# HIVE_BOARD_TOP.net
KiCad netlist of a schematic drawn in Altium Designer
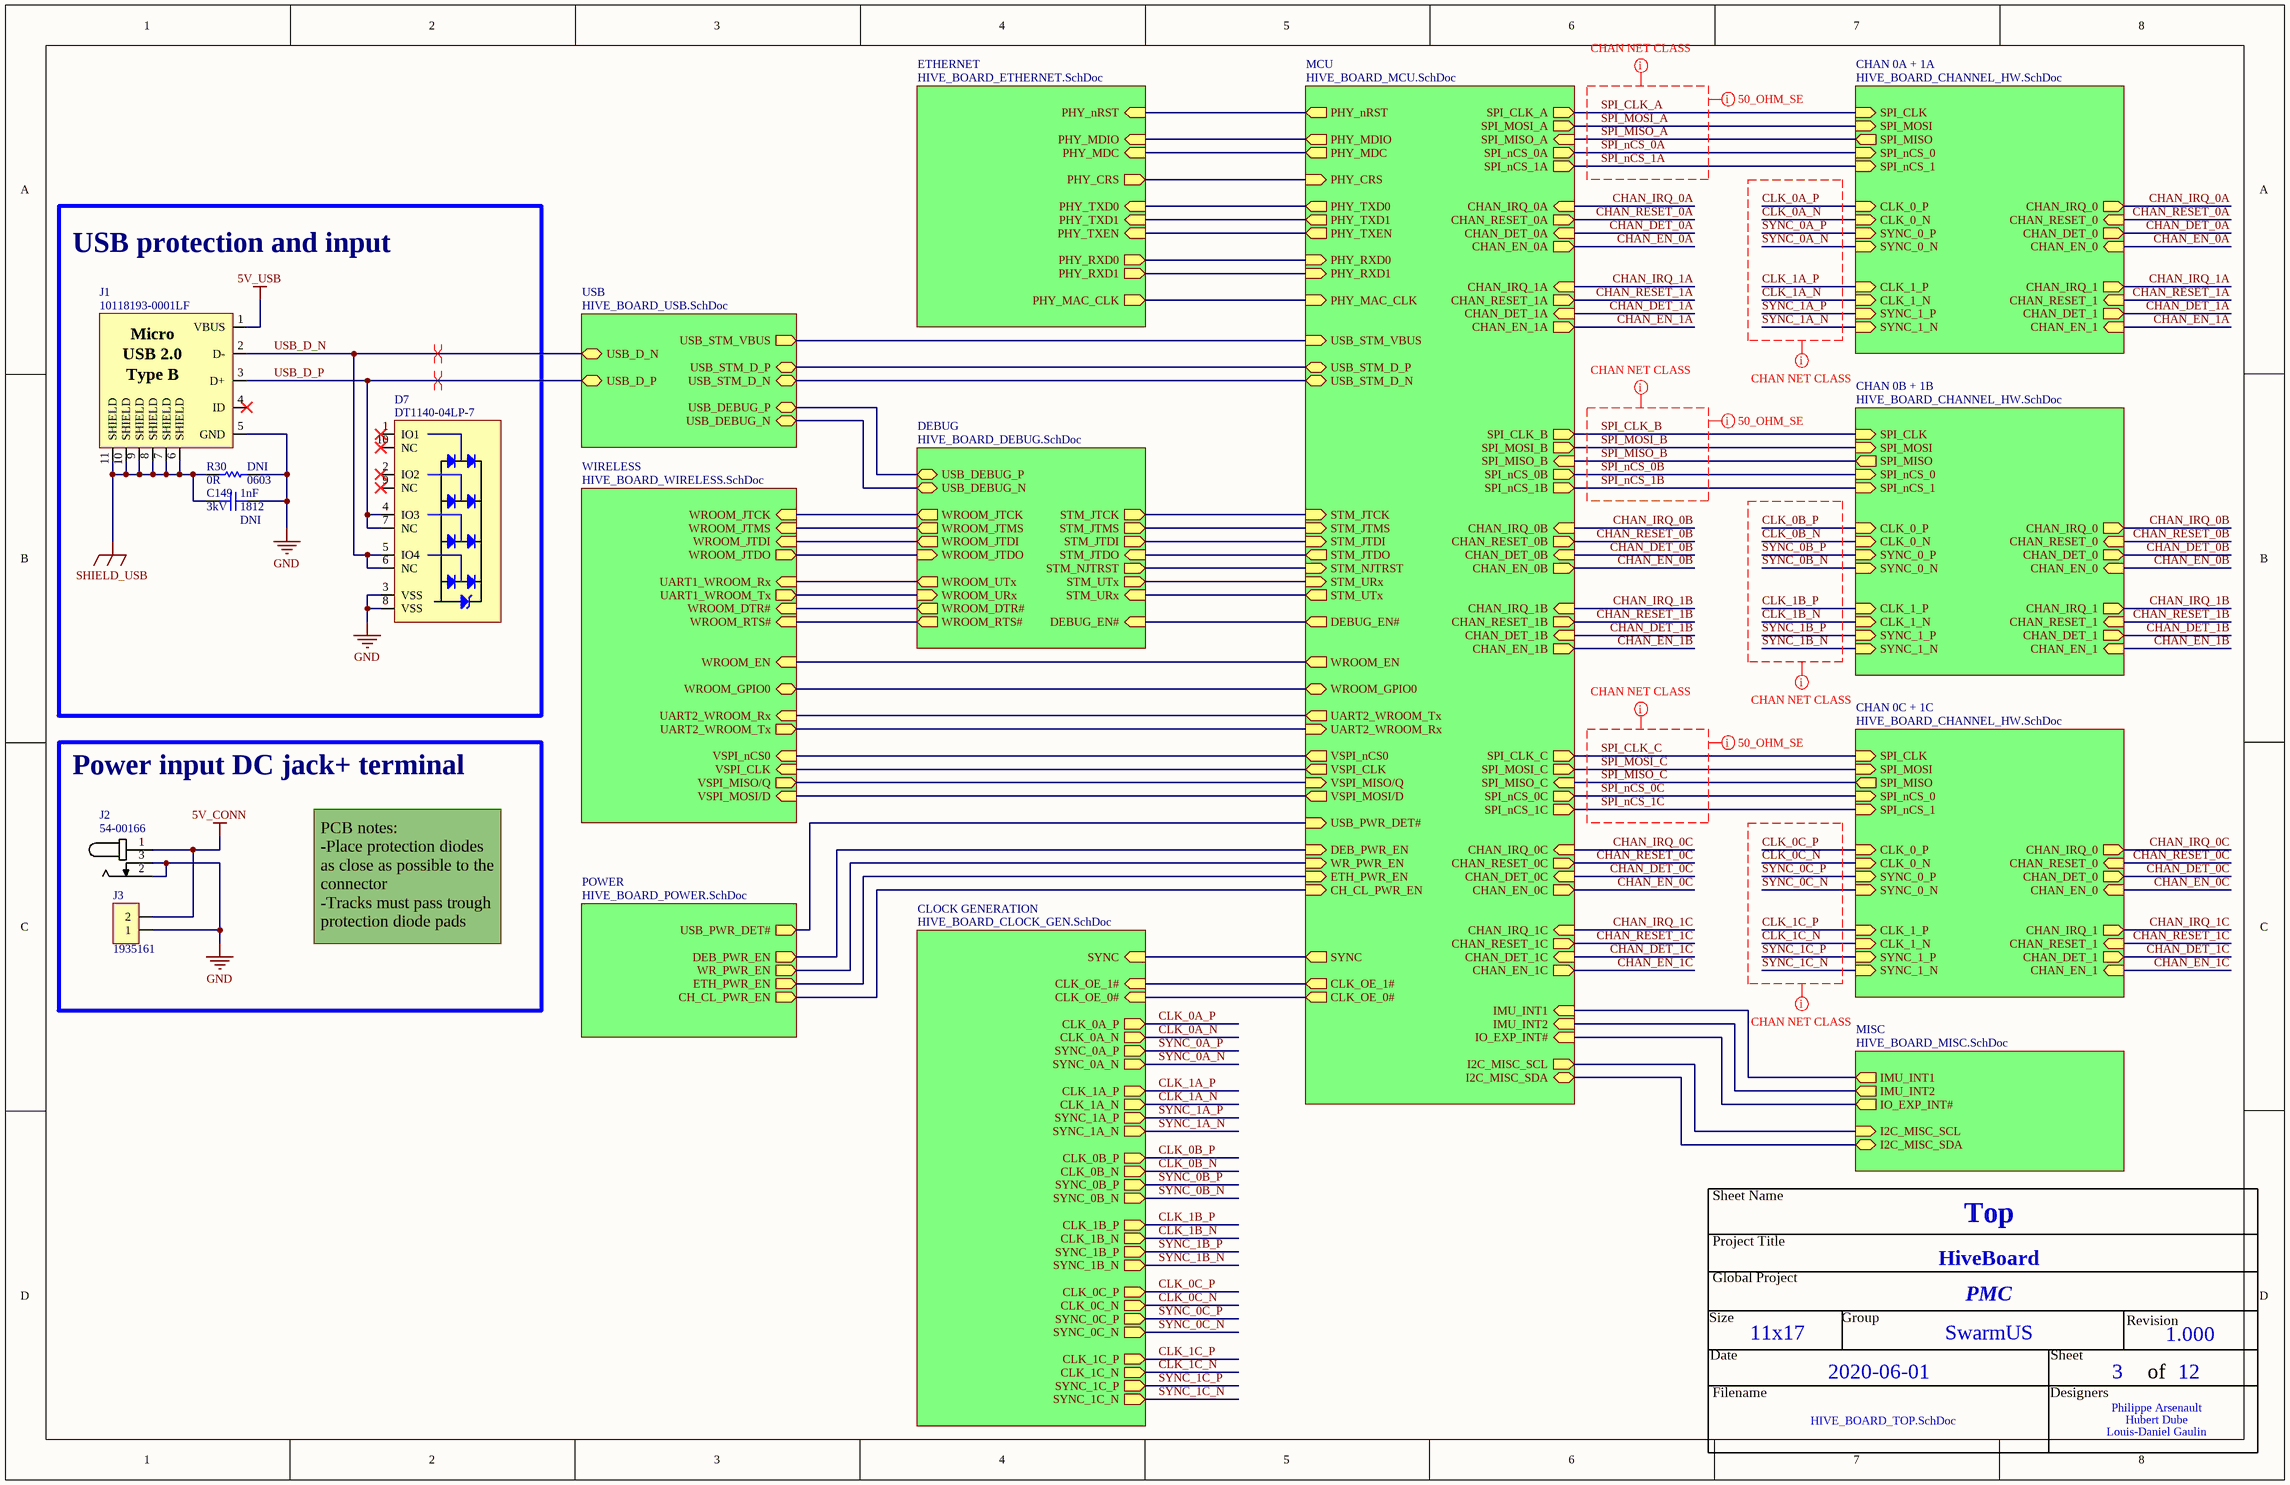
[diagram p0: HIVE_BOARD_TOP.SchDoc]

(export (version "E")
  (design (tool "Eeschema 10.0.6"))
  (components
    (comp (ref "C149")
      (value "1nF")
      (footprint "CAP_CER_1812")
      (description "CAP - CER 1000pF ±10% 3000V X7R")
      (fields
        (field (name "TOLERANCE") "10%")
        (field (name "PACKAGE") "1812")
        (field (name "VOLTAGE RATING") "3kV")
        (field (name "ASSEMBLY NOTE") "DNI")
        (field (name "Comment") "885342211009")
        (field (name "CREATEDBY/DATE") "Hubert Dube - 03/02/2021")
        (field (name "VERIFIEDBY") "Philippe Asenault - 08-02-2021")
      )
      (libsource (lib "SWARMUS_LIB") (part "CAP_CER_885342211009"))
    )
    (comp (ref "D7")
      (value "DT1140-04LP-7")
      (footprint "TVS_DATA_DT1140-04LP-7")
      (description "TVS - DIODE 5.5V 10V - 10-UFDFN")
      (fields
        (field (name "CREATEDBY/DATE") "Joël Lemay 2019-11-20")
        (field (name "VERIFIEDBY") "C.Paulin - 21/11/2019")
      )
      (libsource (lib "GRAMS_MASTER_LIB") (part "TVS_DATA_DT1140-04LP-7"))
    )
    (comp (ref "J1")
      (value "10118193-0001LF")
      (footprint "CON_USB_10118194-0001LF")
      (description "CON - USB MICRO B RECPT SMT R/A - 4PIN")
      (fields
        (field (name "CREATEDBY/DATE") "Louis-Daniel Gaulin / 31-05-2021")
        (field (name "VERIFIEDBY") "Philippe Arsenault/2021-06-07")
      )
      (libsource (lib "SWARMUS_LIB") (part "CON_USB_2.0_MicroB_10118193-0001LF"))
    )
    (comp (ref "J2")
      (value "54-00166")
      (footprint "CON_PWR_PJ-002A")
      (description "CON -  PWR JACK 231X5.5MM SOLDER RIGHT ANGLE - TH")
      (fields
        (field (name "CREATEDBY/DATE") "L-D Gaulin / 23-05-2021")
        (field (name "VERIFIEDBY") "Philippe Arsenault/24-05-2021")
      )
      (libsource (lib "SWARMUS_LIB") (part "CON_PWR_54-00166"))
    )
    (comp (ref "J3")
      (value "1935161")
      (footprint "CON_ 1935161")
      (description "CON - TERM BLK 2POS SIDE ENTRY 5MM PCB - TH - 14-26 AWG")
      (fields
        (field (name "CREATEDBY/DATE") "Louis-Daniel Gaulin / 02-11-2020")
        (field (name "VERIFIEDBY") "Philippe Arsenault/2020-11-06")
      )
      (libsource (lib "SWARMUS_LIB") (part "CON_1935161"))
    )
    (comp (ref "R30")
      (value "0R")
      (footprint "RES_0603")
      (description "RES - 0 ohm jumper 1/10W - 0603")
      (fields
        (field (name "ASSEMBLY NOTE") "DNI")
        (field (name "PACKAGE") "0603")
        (field (name "Comment") "RC0603JR-070RL")
        (field (name "CREATEDBY/DATE") "L-P Gauthier 2018-10-30")
        (field (name "VERIFIEDBY") "Caroline Paulin  - 5/11/2018")
      )
      (libsource (lib "GRAMS_MASTER_LIB") (part "RES_RC0603JR-070RL"))
    )
  )
  (nets
    (net (code "98") (name "/USB_D_N") (class "Default")
      (node (ref "D7") (pin "5") (pinfunction "IO4_5") (pintype "passive"))
      (node (ref "D7") (pin "6") (pinfunction "NC_6") (pintype "passive"))
      (node (ref "J1") (pin "2") (pinfunction "D-_2") (pintype "passive"))
    )
    (net (code "99") (name "/USB_D_P") (class "Default")
      (node (ref "D7") (pin "4") (pinfunction "IO3_4") (pintype "passive"))
      (node (ref "D7") (pin "7") (pinfunction "NC_7") (pintype "passive"))
      (node (ref "J1") (pin "3") (pinfunction "D+_3") (pintype "passive"))
    )
    (net (code "118") (name "5V_CONN") (class "Default")
      (node (ref "J2") (pin "1") (pinfunction "1_1") (pintype "passive"))
      (node (ref "J3") (pin "2") (pinfunction "2_2") (pintype "passive"))
    )
    (net (code "119") (name "5V_USB") (class "Default")
      (node (ref "J1") (pin "1") (pinfunction "VBUS_1") (pintype "passive"))
    )
    (net (code "120") (name "GND") (class "Default")
      (node (ref "C149") (pin "1") (pinfunction "1_1") (pintype "passive"))
      (node (ref "D7") (pin "3") (pinfunction "VSS_3") (pintype "passive"))
      (node (ref "D7") (pin "8") (pinfunction "VSS_8") (pintype "passive"))
      (node (ref "J1") (pin "5") (pinfunction "GND_5") (pintype "passive"))
      (node (ref "J2") (pin "2") (pinfunction "2_2") (pintype "passive"))
      (node (ref "J2") (pin "3") (pinfunction "3_3") (pintype "passive"))
      (node (ref "J3") (pin "1") (pinfunction "1_1") (pintype "passive"))
      (node (ref "R30") (pin "1") (pinfunction "1_1") (pintype "passive"))
    )
    (net (code "121") (name "SHIELD_USB") (class "Default")
      (node (ref "C149") (pin "2") (pinfunction "2_2") (pintype "passive"))
      (node (ref "J1") (pin "10") (pinfunction "SHIELD_10") (pintype "passive"))
      (node (ref "J1") (pin "11") (pinfunction "SHIELD_11") (pintype "passive"))
      (node (ref "J1") (pin "6") (pinfunction "SHIELD_6") (pintype "passive"))
      (node (ref "J1") (pin "7") (pinfunction "SHIELD_7") (pintype "passive"))
      (node (ref "J1") (pin "8") (pinfunction "SHIELD_8") (pintype "passive"))
      (node (ref "J1") (pin "9") (pinfunction "SHIELD_9") (pintype "passive"))
      (node (ref "R30") (pin "2") (pinfunction "2_2") (pintype "passive"))
    )
    (net (code "122") (name "unconnected-(D7-IO1-Pad1)") (class "Default")
      (node (ref "D7") (pin "1") (pinfunction "IO1_1") (pintype "passive+no_connect"))
    )
    (net (code "123") (name "unconnected-(D7-IO2-Pad2)") (class "Default")
      (node (ref "D7") (pin "2") (pinfunction "IO2_2") (pintype "passive+no_connect"))
    )
    (net (code "124") (name "unconnected-(D7-NC-Pad9)") (class "Default")
      (node (ref "D7") (pin "9") (pinfunction "NC_9") (pintype "passive+no_connect"))
    )
    (net (code "125") (name "unconnected-(D7-NC-Pad10)") (class "Default")
      (node (ref "D7") (pin "10") (pinfunction "NC_10") (pintype "passive+no_connect"))
    )
    (net (code "126") (name "unconnected-(J1-ID-Pad4)") (class "Default")
      (node (ref "J1") (pin "4") (pinfunction "ID_4") (pintype "passive+no_connect"))
    )
  )
)
